# Schematic.net
KiCad netlist of a schematic drawn in EAGLE
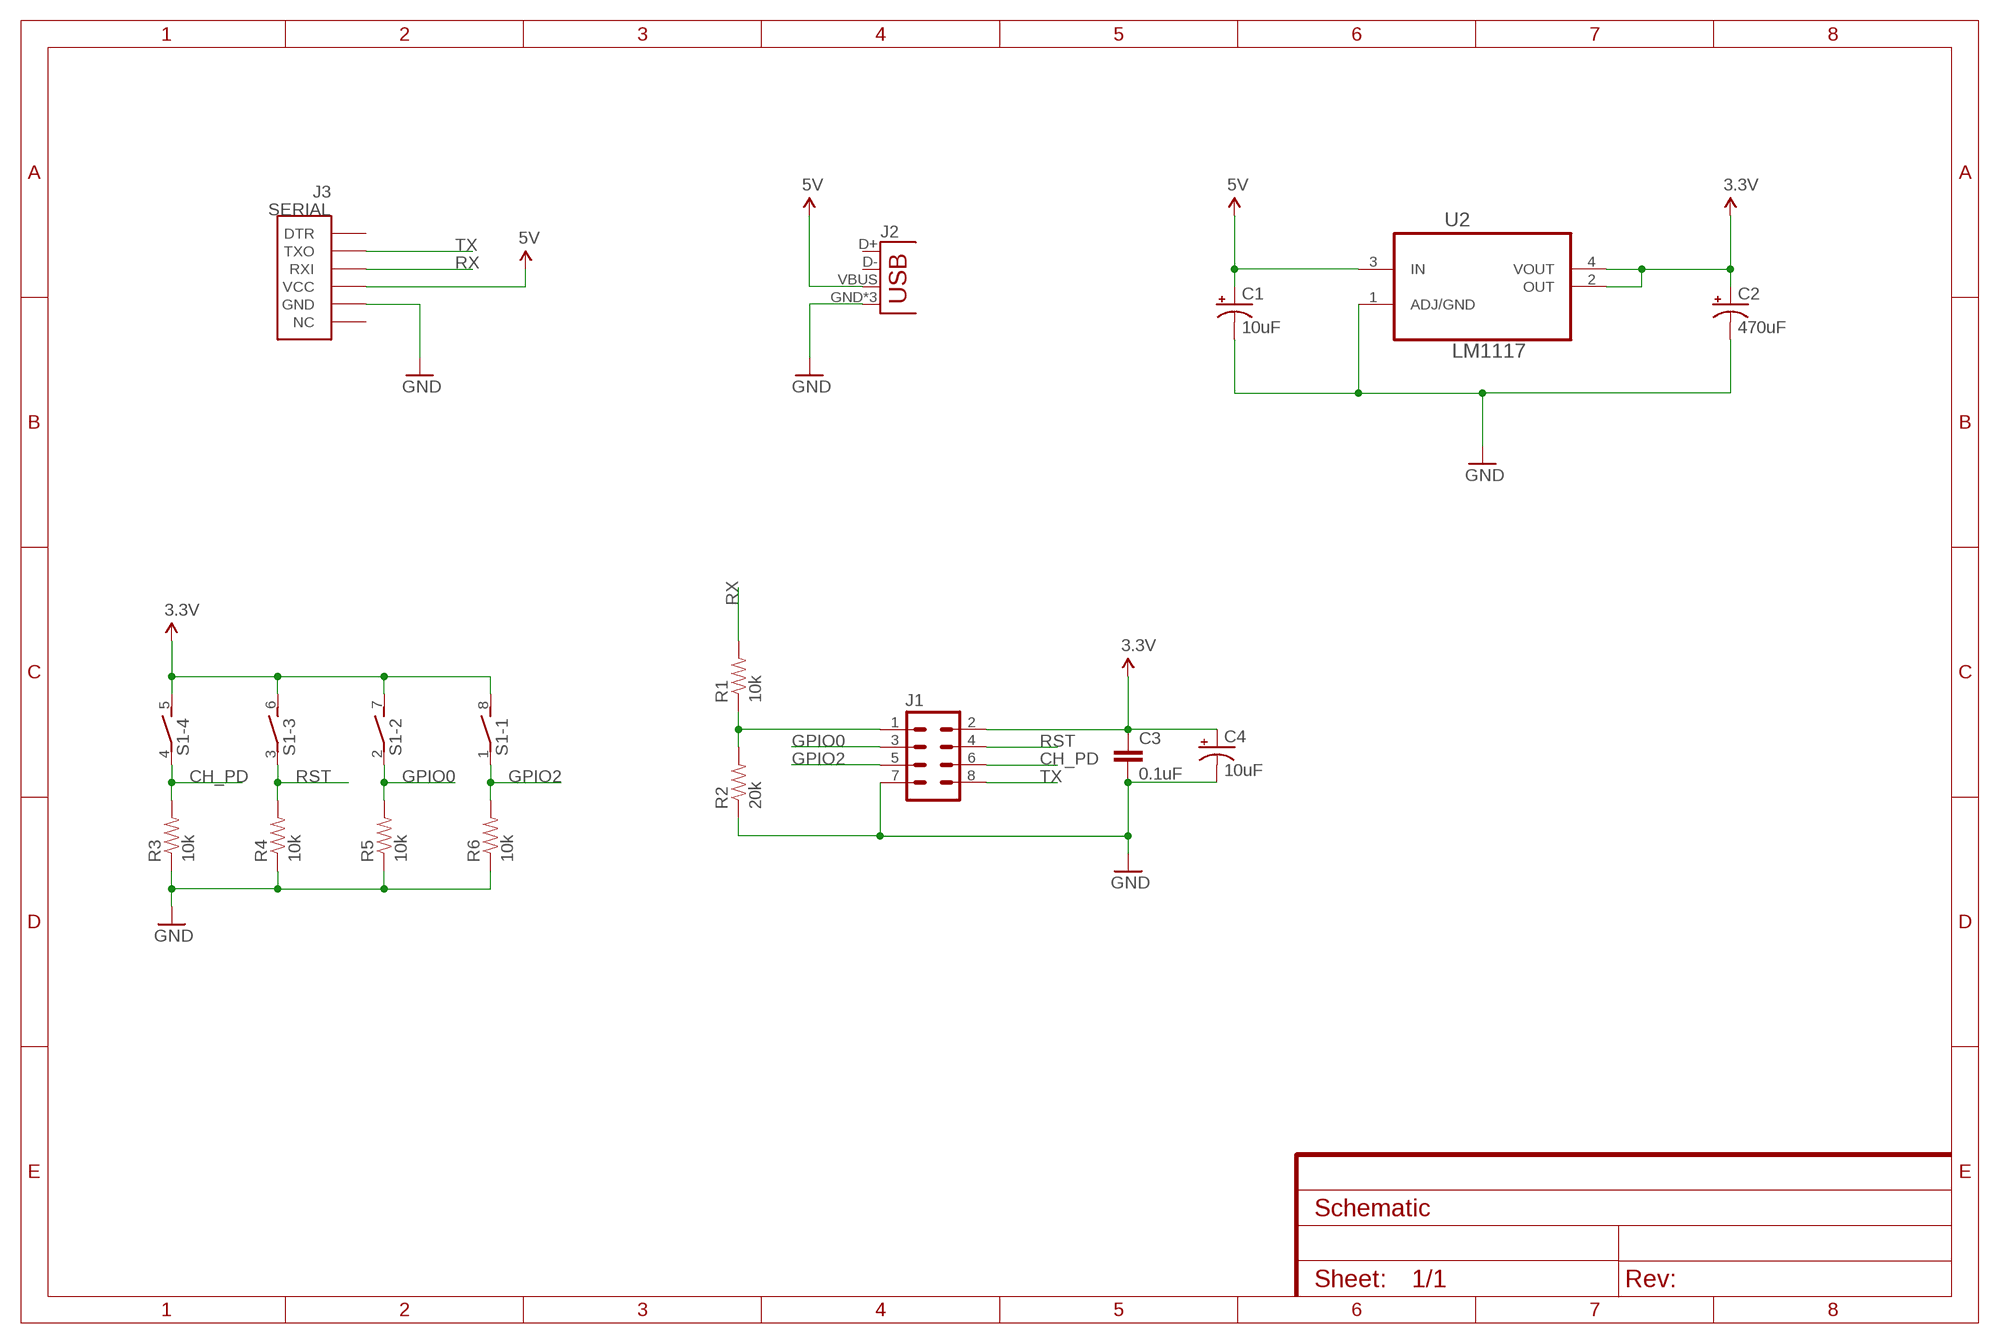
[diagram p0: schematic, sheet 1]

(export (version "E")
  (design (tool "Eeschema 10.0.6"))
  (components
    (comp (ref "C1")
      (value "10uF")
      (footprint "eagle-import:EIA3216-KIT")
      (libsource (lib "eagle-import") (part "CAP_POL1206-KIT"))
    )
    (comp (ref "C2")
      (value "470uF")
      (footprint "eagle-import:CPOL-RADIAL-100UF-25V")
      (libsource (lib "eagle-import") (part "CAP_POLPTH1"))
    )
    (comp (ref "C3")
      (value "0.1uF")
      (footprint "eagle-import:1206")
      (libsource (lib "eagle-import") (part "CAP1206"))
    )
    (comp (ref "C4")
      (value "10uF")
      (footprint "eagle-import:EIA3216-KIT")
      (libsource (lib "eagle-import") (part "CAP_POL1206-KIT"))
    )
    (comp (ref "J1")
      (value "M04X2")
      (footprint "eagle-import:2X4")
      (libsource (lib "eagle-import") (part "M04X2"))
    )
    (comp (ref "J2")
      (value "USB-MICROB")
      (footprint "eagle-import:USB-MICROB")
      (libsource (lib "eagle-import") (part "USB-MICROB"))
    )
    (comp (ref "J3")
      (value "SERIAL")
      (footprint "eagle-import:CP2102_DEVICE_SIDE")
      (libsource (lib "eagle-import") (part "CP2102_DEVICECP"))
    )
    (comp (ref "R1")
      (value "10k")
      (footprint "eagle-import:1206")
      (libsource (lib "eagle-import") (part "RESISTOR1206"))
    )
    (comp (ref "R2")
      (value "20k")
      (footprint "eagle-import:1206")
      (libsource (lib "eagle-import") (part "RESISTOR1206"))
    )
    (comp (ref "R3")
      (value "10k")
      (footprint "eagle-import:1206")
      (libsource (lib "eagle-import") (part "RESISTOR1206"))
    )
    (comp (ref "R4")
      (value "10k")
      (footprint "eagle-import:1206")
      (libsource (lib "eagle-import") (part "RESISTOR1206"))
    )
    (comp (ref "R5")
      (value "10k")
      (footprint "eagle-import:1206")
      (libsource (lib "eagle-import") (part "RESISTOR1206"))
    )
    (comp (ref "R6")
      (value "10k")
      (footprint "eagle-import:1206")
      (libsource (lib "eagle-import") (part "RESISTOR1206"))
    )
    (comp (ref "S1")
      (value "DIP04S")
      (footprint "eagle-import:DIP04S")
      (libsource (lib "eagle-import") (part "DIP04S"))
    )
    (comp (ref "U2")
      (value "LM1117")
      (footprint "eagle-import:SOT230P696X180-4N")
      (fields (field (name "MPN") "LM1117MP-3.3"))
      (libsource (lib "eagle-import") (part "LM1117MP-3.3"))
    )
  )
  (nets
    (net (code "1") (name "/CH_PD") (class "Default")
      (node (ref "J1") (pin "6") (pinfunction "6_6") (pintype "passive"))
      (node (ref "R3") (pin "2") (pinfunction "2_2") (pintype "passive"))
      (node (ref "S1") (pin "4") (pinfunction "1_4") (pintype "passive"))
    )
    (net (code "2") (name "/GPIO0") (class "Default")
      (node (ref "J1") (pin "3") (pinfunction "3_3") (pintype "passive"))
      (node (ref "R5") (pin "2") (pinfunction "2_2") (pintype "passive"))
      (node (ref "S1") (pin "2") (pinfunction "1_2") (pintype "passive"))
    )
    (net (code "3") (name "/GPIO2") (class "Default")
      (node (ref "J1") (pin "5") (pinfunction "5_5") (pintype "passive"))
      (node (ref "R6") (pin "2") (pinfunction "2_2") (pintype "passive"))
      (node (ref "S1") (pin "1") (pinfunction "1_1") (pintype "passive"))
    )
    (net (code "4") (name "/RST") (class "Default")
      (node (ref "J1") (pin "4") (pinfunction "4_4") (pintype "passive"))
      (node (ref "R4") (pin "2") (pinfunction "2_2") (pintype "passive"))
      (node (ref "S1") (pin "3") (pinfunction "1_3") (pintype "passive"))
    )
    (net (code "5") (name "/RX") (class "Default")
      (node (ref "J3") (pin "P$3") (pinfunction "RXI_P$3") (pintype "bidirectional"))
      (node (ref "R1") (pin "2") (pinfunction "2_2") (pintype "passive"))
    )
    (net (code "6") (name "/TX") (class "Default")
      (node (ref "J1") (pin "8") (pinfunction "8_8") (pintype "passive"))
      (node (ref "J3") (pin "P$2") (pinfunction "TXO_P$2") (pintype "bidirectional"))
    )
    (net (code "7") (name "3.3V") (class "Default")
      (node (ref "C2") (pin "1") (pinfunction "+_1") (pintype "passive"))
      (node (ref "C3") (pin "1") (pinfunction "1_1") (pintype "passive"))
      (node (ref "C4") (pin "A") (pinfunction "+_A") (pintype "passive"))
      (node (ref "J1") (pin "2") (pinfunction "2_2") (pintype "passive"))
      (node (ref "S1") (pin "5") (pinfunction "2_5") (pintype "passive"))
      (node (ref "S1") (pin "6") (pinfunction "2_6") (pintype "passive"))
      (node (ref "S1") (pin "7") (pinfunction "2_7") (pintype "passive"))
      (node (ref "S1") (pin "8") (pinfunction "2_8") (pintype "passive"))
      (node (ref "U2") (pin "2") (pinfunction "OUT_2") (pintype "output"))
      (node (ref "U2") (pin "4") (pinfunction "VOUT_4") (pintype "output"))
    )
    (net (code "8") (name "5V") (class "Default")
      (node (ref "C1") (pin "A") (pinfunction "+_A") (pintype "passive"))
      (node (ref "J2") (pin "VBUS") (pinfunction "VBUS_VBUS") (pintype "bidirectional"))
      (node (ref "J3") (pin "P$4") (pinfunction "VCC_P$4") (pintype "bidirectional"))
      (node (ref "U2") (pin "3") (pinfunction "IN_3") (pintype "input"))
    )
    (net (code "9") (name "GND") (class "Default")
      (node (ref "C1") (pin "C") (pinfunction "-_C") (pintype "passive"))
      (node (ref "C2") (pin "2") (pinfunction "-_2") (pintype "passive"))
      (node (ref "C3") (pin "2") (pinfunction "2_2") (pintype "passive"))
      (node (ref "C4") (pin "C") (pinfunction "-_C") (pintype "passive"))
      (node (ref "J1") (pin "7") (pinfunction "7_7") (pintype "passive"))
      (node (ref "J2") (pin "GND") (pinfunction "GND_GND") (pintype "bidirectional"))
      (node (ref "J2") (pin "MT1") (pinfunction "GND_MT1") (pintype "bidirectional"))
      (node (ref "J2") (pin "MT2") (pinfunction "GND_MT2") (pintype "bidirectional"))
      (node (ref "J3") (pin "P$5") (pinfunction "GND_P$5") (pintype "bidirectional"))
      (node (ref "R2") (pin "1") (pinfunction "1_1") (pintype "passive"))
      (node (ref "R3") (pin "1") (pinfunction "1_1") (pintype "passive"))
      (node (ref "R4") (pin "1") (pinfunction "1_1") (pintype "passive"))
      (node (ref "R5") (pin "1") (pinfunction "1_1") (pintype "passive"))
      (node (ref "R6") (pin "1") (pinfunction "1_1") (pintype "passive"))
      (node (ref "U2") (pin "1") (pinfunction "ADJ/GND_1") (pintype "passive"))
    )
    (net (code "10") (name "Net-(J1-Pad1)") (class "Default")
      (node (ref "J1") (pin "1") (pinfunction "1_1") (pintype "passive"))
      (node (ref "R1") (pin "1") (pinfunction "1_1") (pintype "passive"))
      (node (ref "R2") (pin "2") (pinfunction "2_2") (pintype "passive"))
    )
    (net (code "11") (name "unconnected-(J2-PadD+)") (class "Default")
      (node (ref "J2") (pin "D+") (pinfunction "D+_D+") (pintype "bidirectional"))
    )
    (net (code "12") (name "unconnected-(J2-PadD-)") (class "Default")
      (node (ref "J2") (pin "D-") (pinfunction "D-_D-") (pintype "bidirectional"))
    )
    (net (code "13") (name "unconnected-(J3-DTR-PadP$1)") (class "Default")
      (node (ref "J3") (pin "P$1") (pinfunction "DTR_P$1") (pintype "bidirectional"))
    )
    (net (code "14") (name "unconnected-(J3-NC-PadP$6)") (class "Default")
      (node (ref "J3") (pin "P$6") (pinfunction "NC_P$6") (pintype "bidirectional"))
    )
  )
)
